# 3_CAN.net
KiCad netlist of a schematic drawn in Altium Designer
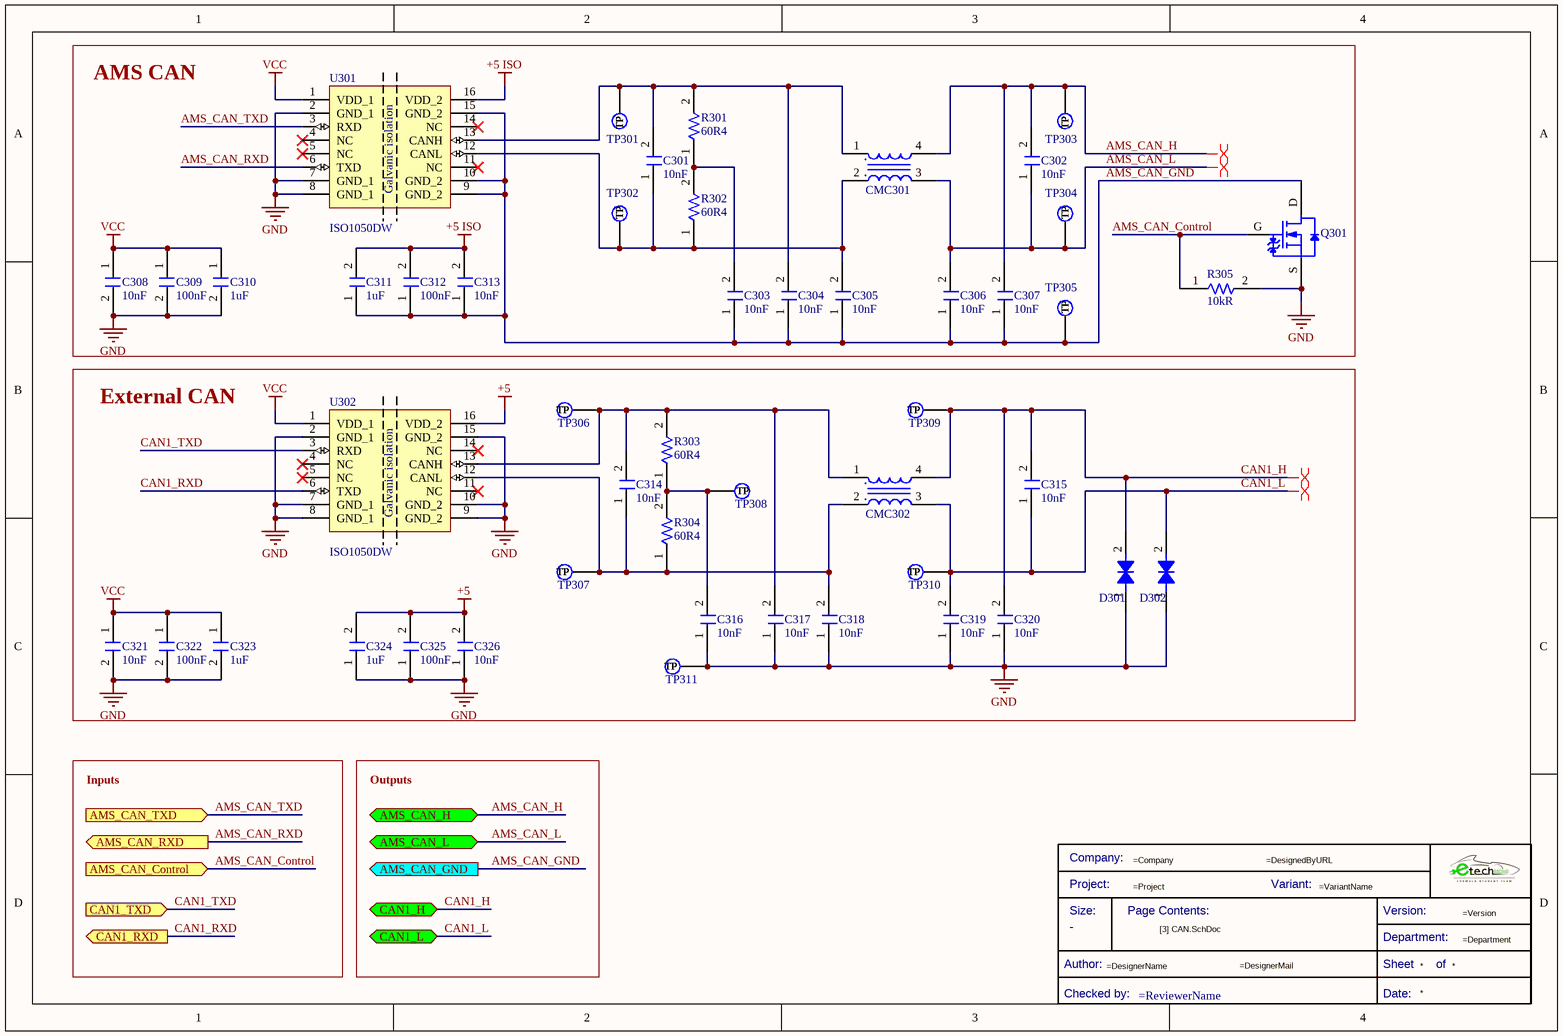
[diagram p0: [3] CAN.SchDoc]

(export (version "E")
  (design (tool "Eeschema 10.0.6"))
  (components
    (comp (ref "*")
      (value "Title Block_template")
      (description "Standard Title Block")
      (fields (field (name "SIZE") "-"))
      (libsource (lib "e-Tech_Racing") (part "Title Block_template"))
    )
    (comp (ref "C301")
      (value "885012207092")
      (footprint "C0805FNPC-R")
      (description "Cap, 0.01ΜF, 50V, 10%, X7R, 0805")
      (fields
        (field (name "TOLERANCE") "10%")
        (field (name "CAPACITANCE") "10nF")
        (field (name ".CREATOR") "DR")
      )
      (libsource (lib "Passives") (part "C10n-50V-0805FNPC-X7R"))
    )
    (comp (ref "C302")
      (value "885012207092")
      (footprint "C0805FNPC-R")
      (description "Cap, 0.01ΜF, 50V, 10%, X7R, 0805")
      (fields
        (field (name "TOLERANCE") "10%")
        (field (name "CAPACITANCE") "10nF")
        (field (name ".CREATOR") "DR")
      )
      (libsource (lib "Passives") (part "C10n-50V-0805FNPC-X7R"))
    )
    (comp (ref "C303")
      (value "885012207092")
      (footprint "C0805FNPC-R")
      (description "Cap, 0.01ΜF, 50V, 10%, X7R, 0805")
      (fields
        (field (name "TOLERANCE") "10%")
        (field (name "CAPACITANCE") "10nF")
        (field (name ".CREATOR") "DR")
      )
      (libsource (lib "Passives") (part "C10n-50V-0805FNPC-X7R"))
    )
    (comp (ref "C304")
      (value "885012207092")
      (footprint "C0805FNPC-R")
      (description "Cap, 0.01ΜF, 50V, 10%, X7R, 0805")
      (fields
        (field (name "TOLERANCE") "10%")
        (field (name "CAPACITANCE") "10nF")
        (field (name ".CREATOR") "DR")
      )
      (libsource (lib "Passives") (part "C10n-50V-0805FNPC-X7R"))
    )
    (comp (ref "C305")
      (value "885012207092")
      (footprint "C0805FNPC-R")
      (description "Cap, 0.01ΜF, 50V, 10%, X7R, 0805")
      (fields
        (field (name "TOLERANCE") "10%")
        (field (name "CAPACITANCE") "10nF")
        (field (name ".CREATOR") "DR")
      )
      (libsource (lib "Passives") (part "C10n-50V-0805FNPC-X7R"))
    )
    (comp (ref "C306")
      (value "885012207092")
      (footprint "C0805FNPC-R")
      (description "Cap, 0.01ΜF, 50V, 10%, X7R, 0805")
      (fields
        (field (name "TOLERANCE") "10%")
        (field (name "CAPACITANCE") "10nF")
        (field (name ".CREATOR") "DR")
      )
      (libsource (lib "Passives") (part "C10n-50V-0805FNPC-X7R"))
    )
    (comp (ref "C307")
      (value "885012207092")
      (footprint "C0805FNPC-R")
      (description "Cap, 0.01ΜF, 50V, 10%, X7R, 0805")
      (fields
        (field (name "TOLERANCE") "10%")
        (field (name "CAPACITANCE") "10nF")
        (field (name ".CREATOR") "DR")
      )
      (libsource (lib "Passives") (part "C10n-50V-0805FNPC-X7R"))
    )
    (comp (ref "C308")
      (value "885012207092")
      (footprint "C0805FNPC-R")
      (description "Cap, 0.01ΜF, 50V, 10%, X7R, 0805")
      (fields
        (field (name "TOLERANCE") "10%")
        (field (name "CAPACITANCE") "10nF")
        (field (name ".CREATOR") "DR")
      )
      (libsource (lib "Passives") (part "C10n-50V-0805FNPC-X7R"))
    )
    (comp (ref "C309")
      (value "885012207098")
      (footprint "C0805FNPC-R")
      (description "Cap, 0.1ΜF, 50V, 10%, X7R, 0805")
      (fields
        (field (name "TOLERANCE") "10%")
        (field (name "CAPACITANCE") "100nF")
        (field (name ".CREATOR") "DR")
      )
      (libsource (lib "Passives") (part "C100n-50V-0805FNPC-X7R"))
    )
    (comp (ref "C310")
      (value "885012207103")
      (footprint "C0805FNPC-R")
      (fields
        (field (name "TOLERANCE") "10%")
        (field (name "CAPACITANCE") "1uF")
        (field (name ".CREATOR") "GP")
      )
      (libsource (lib "Passives") (part "C1u-50V-0805FNPC-X7R"))
    )
    (comp (ref "C311")
      (value "885012207103")
      (footprint "C0805FNPC-R")
      (fields
        (field (name "TOLERANCE") "10%")
        (field (name "CAPACITANCE") "1uF")
        (field (name ".CREATOR") "GP")
      )
      (libsource (lib "Passives") (part "C1u-50V-0805FNPC-X7R"))
    )
    (comp (ref "C312")
      (value "885012207098")
      (footprint "C0805FNPC-R")
      (description "Cap, 0.1ΜF, 50V, 10%, X7R, 0805")
      (fields
        (field (name "TOLERANCE") "10%")
        (field (name "CAPACITANCE") "100nF")
        (field (name ".CREATOR") "DR")
      )
      (libsource (lib "Passives") (part "C100n-50V-0805FNPC-X7R"))
    )
    (comp (ref "C313")
      (value "885012207092")
      (footprint "C0805FNPC-R")
      (description "Cap, 0.01ΜF, 50V, 10%, X7R, 0805")
      (fields
        (field (name "TOLERANCE") "10%")
        (field (name "CAPACITANCE") "10nF")
        (field (name ".CREATOR") "DR")
      )
      (libsource (lib "Passives") (part "C10n-50V-0805FNPC-X7R"))
    )
    (comp (ref "C314")
      (value "885012207092")
      (footprint "C0805FNPC-R")
      (description "Cap, 0.01ΜF, 50V, 10%, X7R, 0805")
      (fields
        (field (name "TOLERANCE") "10%")
        (field (name "CAPACITANCE") "10nF")
        (field (name ".CREATOR") "DR")
      )
      (libsource (lib "Passives") (part "C10n-50V-0805FNPC-X7R"))
    )
    (comp (ref "C315")
      (value "885012207092")
      (footprint "C0805FNPC-R")
      (description "Cap, 0.01ΜF, 50V, 10%, X7R, 0805")
      (fields
        (field (name "TOLERANCE") "10%")
        (field (name "CAPACITANCE") "10nF")
        (field (name ".CREATOR") "DR")
      )
      (libsource (lib "Passives") (part "C10n-50V-0805FNPC-X7R"))
    )
    (comp (ref "C316")
      (value "885012207092")
      (footprint "C0805FNPC-R")
      (description "Cap, 0.01ΜF, 50V, 10%, X7R, 0805")
      (fields
        (field (name "TOLERANCE") "10%")
        (field (name "CAPACITANCE") "10nF")
        (field (name ".CREATOR") "DR")
      )
      (libsource (lib "Passives") (part "C10n-50V-0805FNPC-X7R"))
    )
    (comp (ref "C317")
      (value "885012207092")
      (footprint "C0805FNPC-R")
      (description "Cap, 0.01ΜF, 50V, 10%, X7R, 0805")
      (fields
        (field (name "TOLERANCE") "10%")
        (field (name "CAPACITANCE") "10nF")
        (field (name ".CREATOR") "DR")
      )
      (libsource (lib "Passives") (part "C10n-50V-0805FNPC-X7R"))
    )
    (comp (ref "C318")
      (value "885012207092")
      (footprint "C0805FNPC-R")
      (description "Cap, 0.01ΜF, 50V, 10%, X7R, 0805")
      (fields
        (field (name "TOLERANCE") "10%")
        (field (name "CAPACITANCE") "10nF")
        (field (name ".CREATOR") "DR")
      )
      (libsource (lib "Passives") (part "C10n-50V-0805FNPC-X7R"))
    )
    (comp (ref "C319")
      (value "885012207092")
      (footprint "C0805FNPC-R")
      (description "Cap, 0.01ΜF, 50V, 10%, X7R, 0805")
      (fields
        (field (name "TOLERANCE") "10%")
        (field (name "CAPACITANCE") "10nF")
        (field (name ".CREATOR") "DR")
      )
      (libsource (lib "Passives") (part "C10n-50V-0805FNPC-X7R"))
    )
    (comp (ref "C320")
      (value "885012207092")
      (footprint "C0805FNPC-R")
      (description "Cap, 0.01ΜF, 50V, 10%, X7R, 0805")
      (fields
        (field (name "TOLERANCE") "10%")
        (field (name "CAPACITANCE") "10nF")
        (field (name ".CREATOR") "DR")
      )
      (libsource (lib "Passives") (part "C10n-50V-0805FNPC-X7R"))
    )
    (comp (ref "C321")
      (value "885012207092")
      (footprint "C0805FNPC-R")
      (description "Cap, 0.01ΜF, 50V, 10%, X7R, 0805")
      (fields
        (field (name "TOLERANCE") "10%")
        (field (name "CAPACITANCE") "10nF")
        (field (name ".CREATOR") "DR")
      )
      (libsource (lib "Passives") (part "C10n-50V-0805FNPC-X7R"))
    )
    (comp (ref "C322")
      (value "885012207098")
      (footprint "C0805FNPC-R")
      (description "Cap, 0.1ΜF, 50V, 10%, X7R, 0805")
      (fields
        (field (name "TOLERANCE") "10%")
        (field (name "CAPACITANCE") "100nF")
        (field (name ".CREATOR") "DR")
      )
      (libsource (lib "Passives") (part "C100n-50V-0805FNPC-X7R"))
    )
    (comp (ref "C323")
      (value "885012207103")
      (footprint "C0805FNPC-R")
      (fields
        (field (name "TOLERANCE") "10%")
        (field (name "CAPACITANCE") "1uF")
        (field (name ".CREATOR") "GP")
      )
      (libsource (lib "Passives") (part "C1u-50V-0805FNPC-X7R"))
    )
    (comp (ref "C324")
      (value "885012207103")
      (footprint "C0805FNPC-R")
      (fields
        (field (name "TOLERANCE") "10%")
        (field (name "CAPACITANCE") "1uF")
        (field (name ".CREATOR") "GP")
      )
      (libsource (lib "Passives") (part "C1u-50V-0805FNPC-X7R"))
    )
    (comp (ref "C325")
      (value "885012207098")
      (footprint "C0805FNPC-R")
      (description "Cap, 0.1ΜF, 50V, 10%, X7R, 0805")
      (fields
        (field (name "TOLERANCE") "10%")
        (field (name "CAPACITANCE") "100nF")
        (field (name ".CREATOR") "DR")
      )
      (libsource (lib "Passives") (part "C100n-50V-0805FNPC-X7R"))
    )
    (comp (ref "C326")
      (value "885012207092")
      (footprint "C0805FNPC-R")
      (description "Cap, 0.01ΜF, 50V, 10%, X7R, 0805")
      (fields
        (field (name "TOLERANCE") "10%")
        (field (name "CAPACITANCE") "10nF")
        (field (name ".CREATOR") "DR")
      )
      (libsource (lib "Passives") (part "C10n-50V-0805FNPC-X7R"))
    )
    (comp (ref "CMC301")
      (value "744226")
      (footprint "CMC_10u_1.6A")
      (description "Common Mode Chokes Dual 10uH 920Ohm 1kHz 1.6A 80mOhm DCR SMD T/R")
      (fields
        (field (name "MANUFACTURER") "Wurth Electronics")
        (field (name "TOLERANCE") "30%")
        (field (name ".CREATOR") "GP")
      )
      (libsource (lib "Filter components") (part "CMC_10u_1.6A"))
    )
    (comp (ref "CMC302")
      (value "744226")
      (footprint "CMC_10u_1.6A")
      (description "Common Mode Chokes Dual 10uH 920Ohm 1kHz 1.6A 80mOhm DCR SMD T/R")
      (fields
        (field (name "MANUFACTURER") "Wurth Electronics")
        (field (name "TOLERANCE") "30%")
        (field (name ".CREATOR") "GP")
      )
      (libsource (lib "Filter components") (part "CMC_10u_1.6A"))
    )
    (comp (ref "D301")
      (value "824501600")
      (footprint "DTVS-DO-214AC")
      (description "TVS diode [Würth Elektronik] 824501600 TVS diode")
      (fields (field (name "MANUFACTURER") "Wurth Electronics") (field (name ".CREATOR") "DO"))
      (libsource (lib "Filter components") (part "DTVS-6V-DO-214AC"))
    )
    (comp (ref "D302")
      (value "824501600")
      (footprint "DTVS-DO-214AC")
      (description "TVS diode [Würth Elektronik] 824501600 TVS diode")
      (fields (field (name "MANUFACTURER") "Wurth Electronics") (field (name ".CREATOR") "DO"))
      (libsource (lib "Filter components") (part "DTVS-6V-DO-214AC"))
    )
    (comp (ref "Q301")
      (value "CPH3455-TL-H")
      (footprint "TRT-NCH-3/35-CPH")
      (description "CPH3455-TL-H N-channel MOSFET Transistor; 3 A; 35 V; 3-Pin CPH")
      (fields (field (name "MANUFACTURER") "ON Semiconductor") (field (name ".CREATOR") "GP"))
      (libsource (lib "Semiconductor") (part "TRT-NCH-3/35-CPH"))
    )
    (comp (ref "R301")
      (value "60R4")
      (footprint "R0805FTK")
      (description "Res Thin Film 0805 60.4 Ohm 0.1% 1/8W ±25ppm/°C Molded SMD SMD Punched Carrier T/R")
      (fields
        (field (name "TOLERANCE") "0.1%")
        (field (name "Comment") "R60-0805FTN")
        (field (name ".CREATOR") "DR")
      )
      (libsource (lib "Passives") (part "R60-0805FTN"))
    )
    (comp (ref "R302")
      (value "60R4")
      (footprint "R0805FTK")
      (description "Res Thin Film 0805 60.4 Ohm 0.1% 1/8W ±25ppm/°C Molded SMD SMD Punched Carrier T/R")
      (fields
        (field (name "TOLERANCE") "0.1%")
        (field (name "Comment") "R60-0805FTN")
        (field (name ".CREATOR") "DR")
      )
      (libsource (lib "Passives") (part "R60-0805FTN"))
    )
    (comp (ref "R303")
      (value "60R4")
      (footprint "R0805FTK")
      (description "Res Thin Film 0805 60.4 Ohm 0.1% 1/8W ±25ppm/°C Molded SMD SMD Punched Carrier T/R")
      (fields
        (field (name "TOLERANCE") "0.1%")
        (field (name "Comment") "R60-0805FTN")
        (field (name ".CREATOR") "DR")
      )
      (libsource (lib "Passives") (part "R60-0805FTN"))
    )
    (comp (ref "R304")
      (value "60R4")
      (footprint "R0805FTK")
      (description "Res Thin Film 0805 60.4 Ohm 0.1% 1/8W ±25ppm/°C Molded SMD SMD Punched Carrier T/R")
      (fields
        (field (name "TOLERANCE") "0.1%")
        (field (name "Comment") "R60-0805FTN")
        (field (name ".CREATOR") "DR")
      )
      (libsource (lib "Passives") (part "R60-0805FTN"))
    )
    (comp (ref "R305")
      (value "CR0805-JW-103ELF")
      (footprint "R0805FTK")
      (fields
        (field (name "TOLERANCE") "5%")
        (field (name "RESISTANCE") "10kR")
        (field (name ".CREATOR") "DR")
      )
      (libsource (lib "Passives") (part "R10k-0805FTK"))
    )
    (comp (ref "TP301")
      (value "TestPoint")
      (footprint "TestPoint")
      (description "Test Point 1x1 mm")
      (fields (field (name ".CREATOR") "GP") (field (name ".PCBCHECK") "GP") (field (name ".SCHCHECK") "GP"))
      (libsource (lib "e-Tech_Racing") (part "TestPoint"))
    )
    (comp (ref "TP302")
      (value "TestPoint")
      (footprint "TestPoint")
      (description "Test Point 1x1 mm")
      (fields (field (name ".CREATOR") "GP") (field (name ".PCBCHECK") "GP") (field (name ".SCHCHECK") "GP"))
      (libsource (lib "e-Tech_Racing") (part "TestPoint"))
    )
    (comp (ref "TP303")
      (value "TestPoint")
      (footprint "TestPoint")
      (description "Test Point 1x1 mm")
      (fields (field (name ".CREATOR") "GP") (field (name ".PCBCHECK") "GP") (field (name ".SCHCHECK") "GP"))
      (libsource (lib "e-Tech_Racing") (part "TestPoint"))
    )
    (comp (ref "TP304")
      (value "TestPoint")
      (footprint "TestPoint")
      (description "Test Point 1x1 mm")
      (fields (field (name ".CREATOR") "GP") (field (name ".PCBCHECK") "GP") (field (name ".SCHCHECK") "GP"))
      (libsource (lib "e-Tech_Racing") (part "TestPoint"))
    )
    (comp (ref "TP305")
      (value "TestPoint")
      (footprint "TestPoint")
      (description "Test Point 1x1 mm")
      (fields (field (name ".CREATOR") "GP") (field (name ".PCBCHECK") "GP") (field (name ".SCHCHECK") "GP"))
      (libsource (lib "e-Tech_Racing") (part "TestPoint"))
    )
    (comp (ref "TP306")
      (value "TestPoint")
      (footprint "TestPoint")
      (description "Test Point 1x1 mm")
      (fields (field (name ".CREATOR") "GP") (field (name ".PCBCHECK") "GP") (field (name ".SCHCHECK") "GP"))
      (libsource (lib "e-Tech_Racing") (part "TestPoint"))
    )
    (comp (ref "TP307")
      (value "TestPoint")
      (footprint "TestPoint")
      (description "Test Point 1x1 mm")
      (fields (field (name ".CREATOR") "GP") (field (name ".PCBCHECK") "GP") (field (name ".SCHCHECK") "GP"))
      (libsource (lib "e-Tech_Racing") (part "TestPoint"))
    )
    (comp (ref "TP308")
      (value "TestPoint")
      (footprint "TestPoint")
      (description "Test Point 1x1 mm")
      (fields (field (name ".CREATOR") "GP") (field (name ".PCBCHECK") "GP") (field (name ".SCHCHECK") "GP"))
      (libsource (lib "e-Tech_Racing") (part "TestPoint"))
    )
    (comp (ref "TP309")
      (value "TestPoint")
      (footprint "TestPoint")
      (description "Test Point 1x1 mm")
      (fields (field (name ".CREATOR") "GP") (field (name ".PCBCHECK") "GP") (field (name ".SCHCHECK") "GP"))
      (libsource (lib "e-Tech_Racing") (part "TestPoint"))
    )
    (comp (ref "TP310")
      (value "TestPoint")
      (footprint "TestPoint")
      (description "Test Point 1x1 mm")
      (fields (field (name ".CREATOR") "GP") (field (name ".PCBCHECK") "GP") (field (name ".SCHCHECK") "GP"))
      (libsource (lib "e-Tech_Racing") (part "TestPoint"))
    )
    (comp (ref "TP311")
      (value "TestPoint")
      (footprint "TestPoint")
      (description "Test Point 1x1 mm")
      (fields (field (name ".CREATOR") "GP") (field (name ".PCBCHECK") "GP") (field (name ".SCHCHECK") "GP"))
      (libsource (lib "e-Tech_Racing") (part "TestPoint"))
    )
    (comp (ref "U301")
      (value "ISO1050DW")
      (footprint "TRANSCEIVER_CAN_SOIC16")
      (description "Isolated 5-V CAN transceiver 16-SOIC -55 to 105")
      (fields (field (name "SUPPLIER PART NUMBER 1") "ISO1050DW") (field (name ".CREATOR") "DR"))
      (libsource (lib "Integrated circuits") (part "Transceiver_CAN_ISO1050"))
    )
    (comp (ref "U302")
      (value "ISO1050DW")
      (footprint "TRANSCEIVER_CAN_SOIC16")
      (description "Isolated 5-V CAN transceiver 16-SOIC -55 to 105")
      (fields (field (name "SUPPLIER PART NUMBER 1") "ISO1050DW") (field (name ".CREATOR") "DR"))
      (libsource (lib "Integrated circuits") (part "Transceiver_CAN_ISO1050"))
    )
  )
  (nets
    (net (code "1") (name "+5") (class "Default")
      (node (ref "C324") (pin "2") (pinfunction "2_2") (pintype "passive"))
      (node (ref "C325") (pin "2") (pinfunction "2_2") (pintype "passive"))
      (node (ref "C326") (pin "2") (pinfunction "2_2") (pintype "passive"))
      (node (ref "U302") (pin "16") (pinfunction "VDD_2_16") (pintype "passive"))
    )
    (net (code "2") (name "+5 ISO") (class "Default")
      (node (ref "C311") (pin "2") (pinfunction "2_2") (pintype "passive"))
      (node (ref "C312") (pin "2") (pinfunction "2_2") (pintype "passive"))
      (node (ref "C313") (pin "2") (pinfunction "2_2") (pintype "passive"))
      (node (ref "U301") (pin "16") (pinfunction "VDD_2_16") (pintype "passive"))
    )
    (net (code "3") (name "/AMS_CAN_Control") (class "Default")
      (node (ref "Q301") (pin "G") (pinfunction "G_G") (pintype "passive"))
      (node (ref "R305") (pin "1") (pinfunction "1_1") (pintype "passive"))
    )
    (net (code "4") (name "/AMS_CAN_GND") (class "Default")
      (node (ref "C303") (pin "1") (pinfunction "1_1") (pintype "passive"))
      (node (ref "C304") (pin "1") (pinfunction "1_1") (pintype "passive"))
      (node (ref "C305") (pin "1") (pinfunction "1_1") (pintype "passive"))
      (node (ref "C306") (pin "1") (pinfunction "1_1") (pintype "passive"))
      (node (ref "C307") (pin "1") (pinfunction "1_1") (pintype "passive"))
      (node (ref "C311") (pin "1") (pinfunction "1_1") (pintype "passive"))
      (node (ref "C312") (pin "1") (pinfunction "1_1") (pintype "passive"))
      (node (ref "C313") (pin "1") (pinfunction "1_1") (pintype "passive"))
      (node (ref "Q301") (pin "D") (pinfunction "D_D") (pintype "passive"))
      (node (ref "TP305") (pin "1") (pinfunction "TP_1") (pintype "passive"))
      (node (ref "U301") (pin "10") (pinfunction "GND_2_10") (pintype "passive"))
      (node (ref "U301") (pin "15") (pinfunction "GND_2_15") (pintype "passive"))
      (node (ref "U301") (pin "9") (pinfunction "GND_2_9") (pintype "passive"))
    )
    (net (code "5") (name "/AMS_CAN_H") (class "Default")
      (node (ref "C302") (pin "2") (pinfunction "2_2") (pintype "passive"))
      (node (ref "C307") (pin "2") (pinfunction "2_2") (pintype "passive"))
      (node (ref "CMC301") (pin "4") (pinfunction "4_OUT_4") (pintype "passive"))
      (node (ref "TP303") (pin "1") (pinfunction "TP_1") (pintype "passive"))
    )
    (net (code "6") (name "/AMS_CAN_L") (class "Default")
      (node (ref "C302") (pin "1") (pinfunction "1_1") (pintype "passive"))
      (node (ref "C306") (pin "2") (pinfunction "2_2") (pintype "passive"))
      (node (ref "CMC301") (pin "3") (pinfunction "3_OUT_3") (pintype "passive"))
      (node (ref "TP304") (pin "1") (pinfunction "TP_1") (pintype "passive"))
    )
    (net (code "7") (name "/AMS_CAN_RXD") (class "Default")
      (node (ref "U301") (pin "6") (pinfunction "TXD_6") (pintype "bidirectional"))
    )
    (net (code "8") (name "/AMS_CAN_TXD") (class "Default")
      (node (ref "U301") (pin "3") (pinfunction "RXD_3") (pintype "bidirectional"))
    )
    (net (code "9") (name "/CAN1_H") (class "Default")
      (node (ref "C315") (pin "2") (pinfunction "2_2") (pintype "passive"))
      (node (ref "C320") (pin "2") (pinfunction "2_2") (pintype "passive"))
      (node (ref "CMC302") (pin "4") (pinfunction "4_OUT_4") (pintype "passive"))
      (node (ref "D301") (pin "2") (pinfunction "2_2") (pintype "passive"))
      (node (ref "TP309") (pin "1") (pinfunction "TP_1") (pintype "passive"))
    )
    (net (code "10") (name "/CAN1_L") (class "Default")
      (node (ref "C315") (pin "1") (pinfunction "1_1") (pintype "passive"))
      (node (ref "C319") (pin "2") (pinfunction "2_2") (pintype "passive"))
      (node (ref "CMC302") (pin "3") (pinfunction "3_OUT_3") (pintype "passive"))
      (node (ref "D302") (pin "2") (pinfunction "2_2") (pintype "passive"))
      (node (ref "TP310") (pin "1") (pinfunction "TP_1") (pintype "passive"))
    )
    (net (code "11") (name "/CAN1_RXD") (class "Default")
      (node (ref "U302") (pin "6") (pinfunction "TXD_6") (pintype "bidirectional"))
    )
    (net (code "12") (name "/CAN1_TXD") (class "Default")
      (node (ref "U302") (pin "3") (pinfunction "RXD_3") (pintype "bidirectional"))
    )
    (net (code "13") (name "GND") (class "Default")
      (node (ref "C308") (pin "2") (pinfunction "2_2") (pintype "passive"))
      (node (ref "C309") (pin "2") (pinfunction "2_2") (pintype "passive"))
      (node (ref "C310") (pin "2") (pinfunction "2_2") (pintype "passive"))
      (node (ref "C316") (pin "1") (pinfunction "1_1") (pintype "passive"))
      (node (ref "C317") (pin "1") (pinfunction "1_1") (pintype "passive"))
      (node (ref "C318") (pin "1") (pinfunction "1_1") (pintype "passive"))
      (node (ref "C319") (pin "1") (pinfunction "1_1") (pintype "passive"))
      (node (ref "C320") (pin "1") (pinfunction "1_1") (pintype "passive"))
      (node (ref "C321") (pin "2") (pinfunction "2_2") (pintype "passive"))
      (node (ref "C322") (pin "2") (pinfunction "2_2") (pintype "passive"))
      (node (ref "C323") (pin "2") (pinfunction "2_2") (pintype "passive"))
      (node (ref "C324") (pin "1") (pinfunction "1_1") (pintype "passive"))
      (node (ref "C325") (pin "1") (pinfunction "1_1") (pintype "passive"))
      (node (ref "C326") (pin "1") (pinfunction "1_1") (pintype "passive"))
      (node (ref "D301") (pin "1") (pinfunction "1_1") (pintype "passive"))
      (node (ref "D302") (pin "1") (pinfunction "1_1") (pintype "passive"))
      (node (ref "Q301") (pin "S") (pinfunction "S_S") (pintype "passive"))
      (node (ref "R305") (pin "2") (pinfunction "2_2") (pintype "passive"))
      (node (ref "TP311") (pin "1") (pinfunction "TP_1") (pintype "passive"))
      (node (ref "U301") (pin "2") (pinfunction "GND_1_2") (pintype "power_in"))
      (node (ref "U301") (pin "7") (pinfunction "GND_1_7") (pintype "passive"))
      (node (ref "U301") (pin "8") (pinfunction "GND_1_8") (pintype "passive"))
      (node (ref "U302") (pin "10") (pinfunction "GND_2_10") (pintype "passive"))
      (node (ref "U302") (pin "15") (pinfunction "GND_2_15") (pintype "passive"))
      (node (ref "U302") (pin "2") (pinfunction "GND_1_2") (pintype "power_in"))
      (node (ref "U302") (pin "7") (pinfunction "GND_1_7") (pintype "passive"))
      (node (ref "U302") (pin "8") (pinfunction "GND_1_8") (pintype "passive"))
      (node (ref "U302") (pin "9") (pinfunction "GND_2_9") (pintype "passive"))
    )
    (net (code "14") (name "Net-(C303-Pad2)") (class "Default")
      (node (ref "C303") (pin "2") (pinfunction "2_2") (pintype "passive"))
      (node (ref "R301") (pin "1") (pinfunction "1_1") (pintype "passive"))
      (node (ref "R302") (pin "2") (pinfunction "2_2") (pintype "passive"))
    )
    (net (code "15") (name "Net-(CMC301-1_IN)") (class "Default")
      (node (ref "C301") (pin "2") (pinfunction "2_2") (pintype "passive"))
      (node (ref "C304") (pin "2") (pinfunction "2_2") (pintype "passive"))
      (node (ref "CMC301") (pin "1") (pinfunction "1_IN_1") (pintype "passive"))
      (node (ref "R301") (pin "2") (pinfunction "2_2") (pintype "passive"))
      (node (ref "TP301") (pin "1") (pinfunction "TP_1") (pintype "passive"))
      (node (ref "U301") (pin "13") (pinfunction "CANH_13") (pintype "bidirectional"))
    )
    (net (code "16") (name "Net-(CMC301-2_IN)") (class "Default")
      (node (ref "C301") (pin "1") (pinfunction "1_1") (pintype "passive"))
      (node (ref "C305") (pin "2") (pinfunction "2_2") (pintype "passive"))
      (node (ref "CMC301") (pin "2") (pinfunction "2_IN_2") (pintype "passive"))
      (node (ref "R302") (pin "1") (pinfunction "1_1") (pintype "passive"))
      (node (ref "TP302") (pin "1") (pinfunction "TP_1") (pintype "passive"))
      (node (ref "U301") (pin "12") (pinfunction "CANL_12") (pintype "bidirectional"))
    )
    (net (code "17") (name "Net-(CMC302-1_IN)") (class "Default")
      (node (ref "C314") (pin "2") (pinfunction "2_2") (pintype "passive"))
      (node (ref "C317") (pin "2") (pinfunction "2_2") (pintype "passive"))
      (node (ref "CMC302") (pin "1") (pinfunction "1_IN_1") (pintype "passive"))
      (node (ref "R303") (pin "2") (pinfunction "2_2") (pintype "passive"))
      (node (ref "TP306") (pin "1") (pinfunction "TP_1") (pintype "passive"))
      (node (ref "U302") (pin "13") (pinfunction "CANH_13") (pintype "bidirectional"))
    )
    (net (code "18") (name "Net-(CMC302-2_IN)") (class "Default")
      (node (ref "C314") (pin "1") (pinfunction "1_1") (pintype "passive"))
      (node (ref "C318") (pin "2") (pinfunction "2_2") (pintype "passive"))
      (node (ref "CMC302") (pin "2") (pinfunction "2_IN_2") (pintype "passive"))
      (node (ref "R304") (pin "1") (pinfunction "1_1") (pintype "passive"))
      (node (ref "TP307") (pin "1") (pinfunction "TP_1") (pintype "passive"))
      (node (ref "U302") (pin "12") (pinfunction "CANL_12") (pintype "bidirectional"))
    )
    (net (code "19") (name "Net-(TP308-TP)") (class "Default")
      (node (ref "C316") (pin "2") (pinfunction "2_2") (pintype "passive"))
      (node (ref "R303") (pin "1") (pinfunction "1_1") (pintype "passive"))
      (node (ref "R304") (pin "2") (pinfunction "2_2") (pintype "passive"))
      (node (ref "TP308") (pin "1") (pinfunction "TP_1") (pintype "passive"))
    )
    (net (code "20") (name "VCC") (class "Default")
      (node (ref "C308") (pin "1") (pinfunction "1_1") (pintype "passive"))
      (node (ref "C309") (pin "1") (pinfunction "1_1") (pintype "passive"))
      (node (ref "C310") (pin "1") (pinfunction "1_1") (pintype "passive"))
      (node (ref "C321") (pin "1") (pinfunction "1_1") (pintype "passive"))
      (node (ref "C322") (pin "1") (pinfunction "1_1") (pintype "passive"))
      (node (ref "C323") (pin "1") (pinfunction "1_1") (pintype "passive"))
      (node (ref "U301") (pin "1") (pinfunction "VDD_1_1") (pintype "open_collector"))
      (node (ref "U302") (pin "1") (pinfunction "VDD_1_1") (pintype "open_collector"))
    )
    (net (code "21") (name "unconnected-(U301-NC-Pad4)") (class "Default")
      (node (ref "U301") (pin "4") (pinfunction "NC_4") (pintype "open_emitter+no_connect"))
    )
    (net (code "22") (name "unconnected-(U301-NC-Pad5)") (class "Default")
      (node (ref "U301") (pin "5") (pinfunction "NC_5") (pintype "passive+no_connect"))
    )
    (net (code "23") (name "unconnected-(U301-NC-Pad11)") (class "Default")
      (node (ref "U301") (pin "11") (pinfunction "NC_11") (pintype "passive+no_connect"))
    )
    (net (code "24") (name "unconnected-(U301-NC-Pad14)") (class "Default")
      (node (ref "U301") (pin "14") (pinfunction "NC_14") (pintype "open_collector+no_connect"))
    )
    (net (code "25") (name "unconnected-(U302-NC-Pad4)") (class "Default")
      (node (ref "U302") (pin "4") (pinfunction "NC_4") (pintype "open_emitter+no_connect"))
    )
    (net (code "26") (name "unconnected-(U302-NC-Pad5)") (class "Default")
      (node (ref "U302") (pin "5") (pinfunction "NC_5") (pintype "passive+no_connect"))
    )
    (net (code "27") (name "unconnected-(U302-NC-Pad11)") (class "Default")
      (node (ref "U302") (pin "11") (pinfunction "NC_11") (pintype "passive+no_connect"))
    )
    (net (code "28") (name "unconnected-(U302-NC-Pad14)") (class "Default")
      (node (ref "U302") (pin "14") (pinfunction "NC_14") (pintype "open_collector+no_connect"))
    )
  )
)
